# 2_waffling60-MXHS-ANSI_matrix.net
KiCad netlist of a schematic drawn in Altium Designer
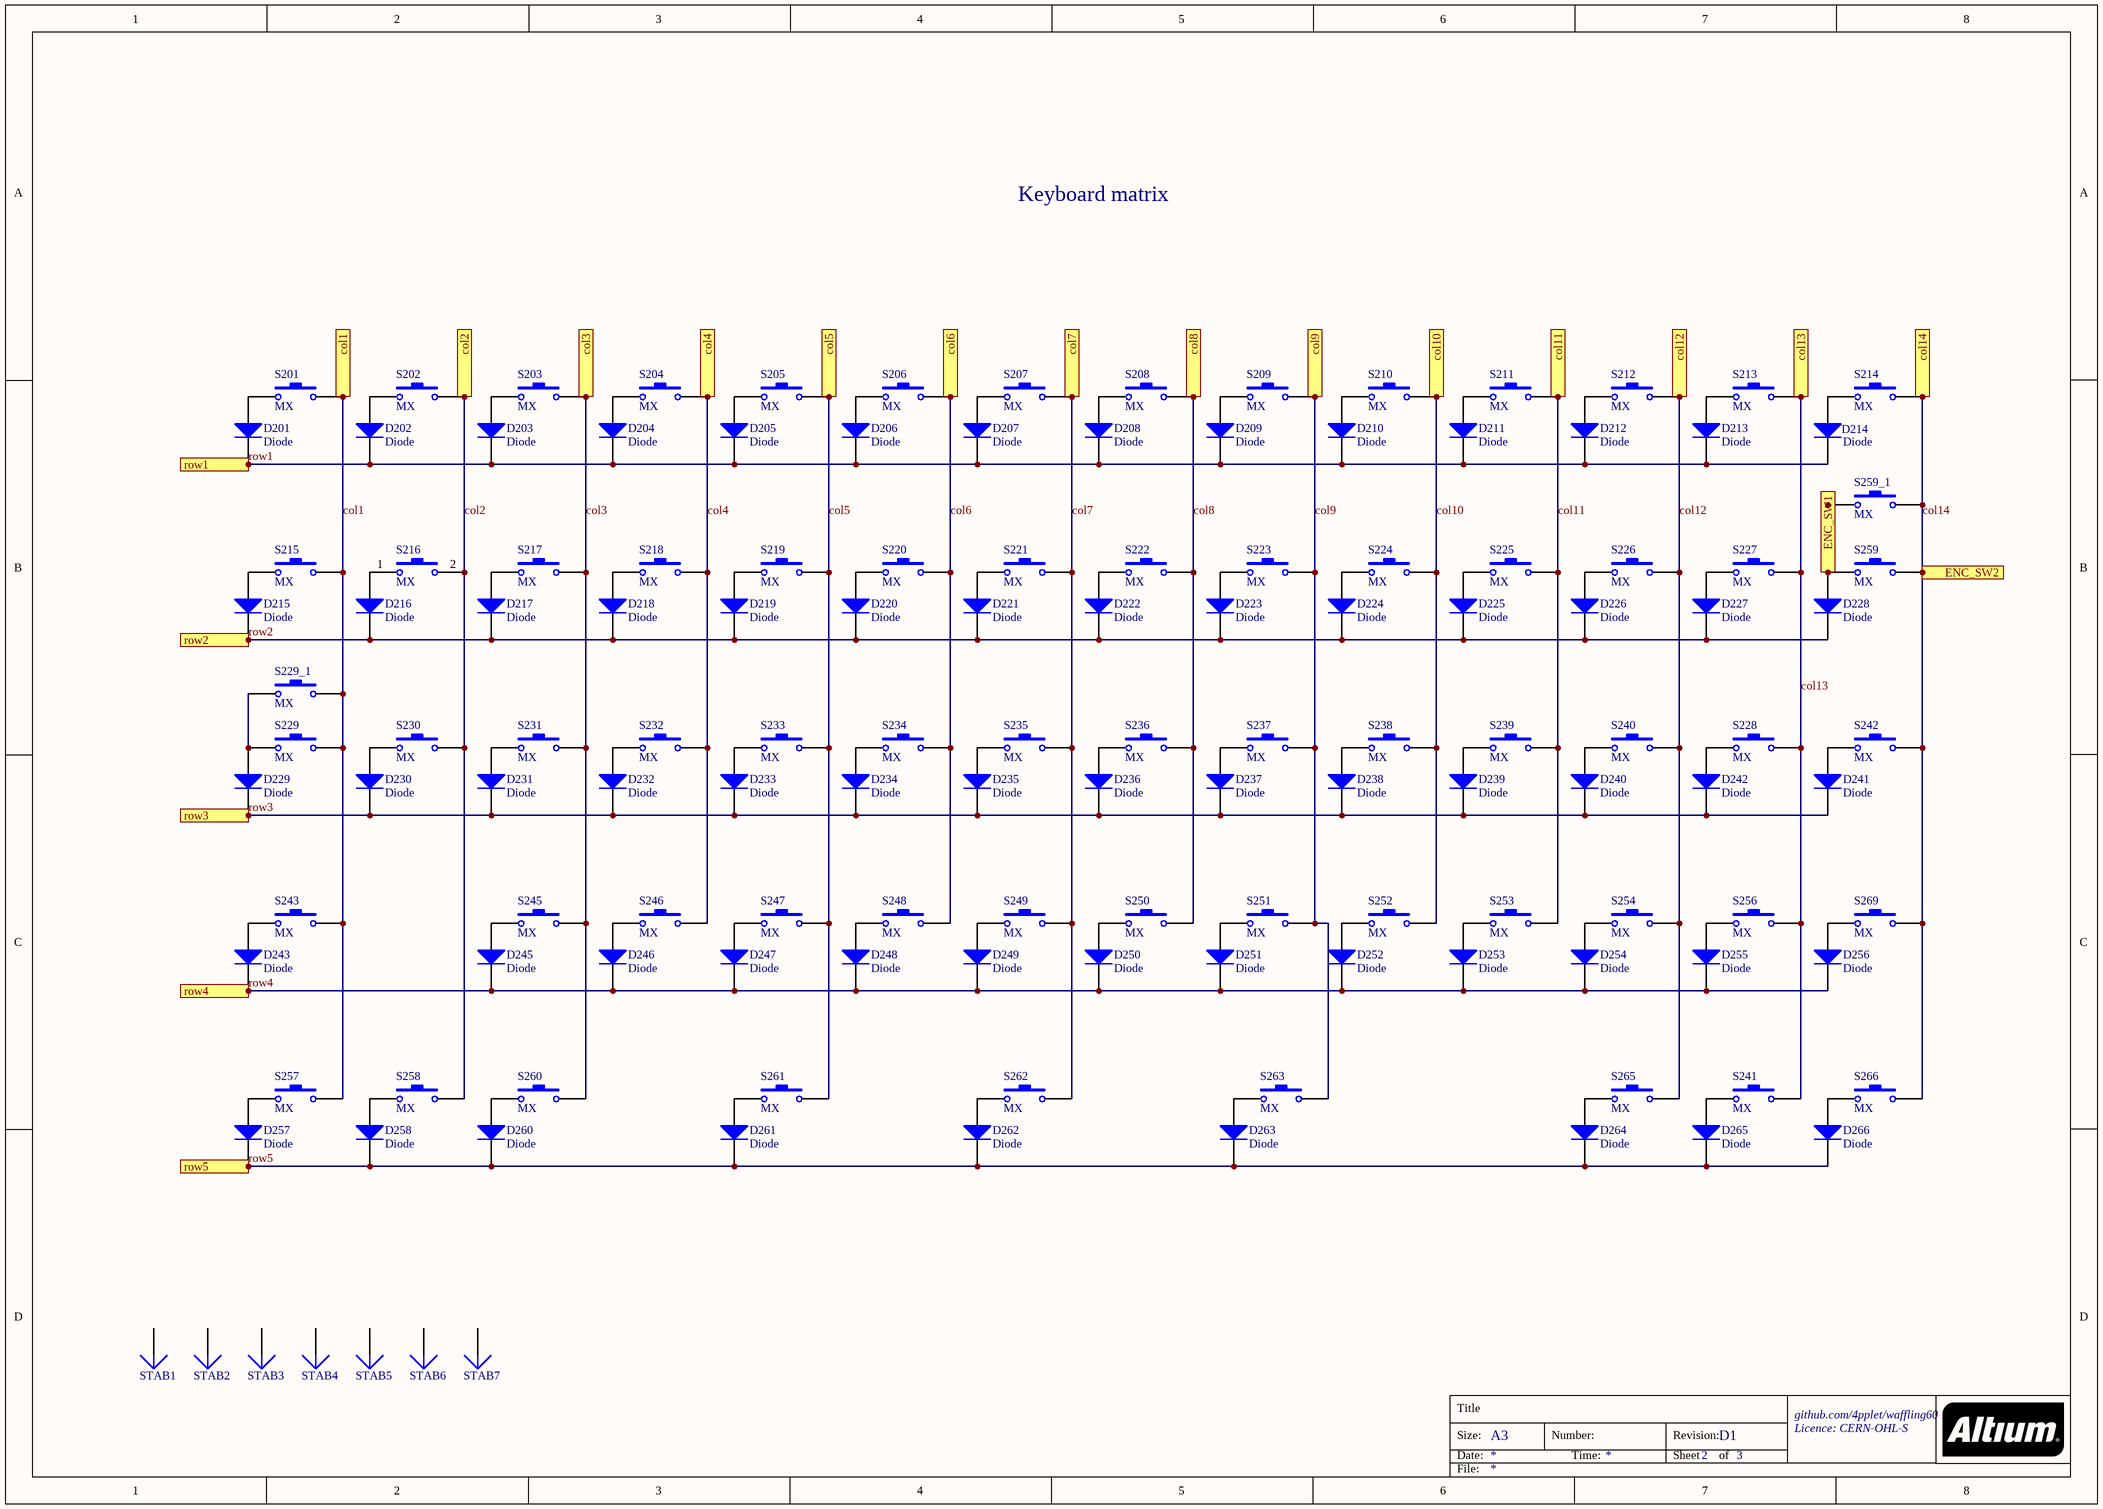
[diagram p0: 2_waffling60-MXHS-ANSI_matrix.SchDoc]

(export (version "E")
  (design (tool "Eeschema 10.0.6"))
  (components
    (comp (ref "D201")
      (value "Diode")
      (footprint "SOD-123")
      (description "Default Diode")
      (fields (field (name "LCSC PART #") "C81598") (field (name "MRF.PART") "1N4148W"))
      (libsource (lib "Miscellaneous Devices") (part "Diode"))
    )
    (comp (ref "D202")
      (value "Diode")
      (footprint "SOD-123")
      (description "Default Diode")
      (fields (field (name "LCSC PART #") "C81598") (field (name "MRF.PART") "1N4148W"))
      (libsource (lib "Miscellaneous Devices") (part "Diode"))
    )
    (comp (ref "D203")
      (value "Diode")
      (footprint "SOD-123")
      (description "Default Diode")
      (fields (field (name "LCSC PART #") "C81598") (field (name "MRF.PART") "1N4148W"))
      (libsource (lib "Miscellaneous Devices") (part "Diode"))
    )
    (comp (ref "D204")
      (value "Diode")
      (footprint "SOD-123")
      (description "Default Diode")
      (fields (field (name "LCSC PART #") "C81598") (field (name "MRF.PART") "1N4148W"))
      (libsource (lib "Miscellaneous Devices") (part "Diode"))
    )
    (comp (ref "D205")
      (value "Diode")
      (footprint "SOD-123")
      (description "Default Diode")
      (fields (field (name "LCSC PART #") "C81598") (field (name "MRF.PART") "1N4148W"))
      (libsource (lib "Miscellaneous Devices") (part "Diode"))
    )
    (comp (ref "D206")
      (value "Diode")
      (footprint "SOD-123")
      (description "Default Diode")
      (fields (field (name "LCSC PART #") "C81598") (field (name "MRF.PART") "1N4148W"))
      (libsource (lib "Miscellaneous Devices") (part "Diode"))
    )
    (comp (ref "D207")
      (value "Diode")
      (footprint "SOD-123")
      (description "Default Diode")
      (fields (field (name "LCSC PART #") "C81598") (field (name "MRF.PART") "1N4148W"))
      (libsource (lib "Miscellaneous Devices") (part "Diode"))
    )
    (comp (ref "D208")
      (value "Diode")
      (footprint "SOD-123")
      (description "Default Diode")
      (fields (field (name "LCSC PART #") "C81598") (field (name "MRF.PART") "1N4148W"))
      (libsource (lib "Miscellaneous Devices") (part "Diode"))
    )
    (comp (ref "D209")
      (value "Diode")
      (footprint "SOD-123")
      (description "Default Diode")
      (fields (field (name "LCSC PART #") "C81598") (field (name "MRF.PART") "1N4148W"))
      (libsource (lib "Miscellaneous Devices") (part "Diode"))
    )
    (comp (ref "D210")
      (value "Diode")
      (footprint "SOD-123")
      (description "Default Diode")
      (fields (field (name "LCSC PART #") "C81598") (field (name "MRF.PART") "1N4148W"))
      (libsource (lib "Miscellaneous Devices") (part "Diode"))
    )
    (comp (ref "D211")
      (value "Diode")
      (footprint "SOD-123")
      (description "Default Diode")
      (fields (field (name "LCSC PART #") "C81598") (field (name "MRF.PART") "1N4148W"))
      (libsource (lib "Miscellaneous Devices") (part "Diode"))
    )
    (comp (ref "D212")
      (value "Diode")
      (footprint "SOD-123")
      (description "Default Diode")
      (fields (field (name "LCSC PART #") "C81598") (field (name "MRF.PART") "1N4148W"))
      (libsource (lib "Miscellaneous Devices") (part "Diode"))
    )
    (comp (ref "D213")
      (value "Diode")
      (footprint "SOD-123")
      (description "Default Diode")
      (fields (field (name "LCSC PART #") "C81598") (field (name "MRF.PART") "1N4148W"))
      (libsource (lib "Miscellaneous Devices") (part "Diode"))
    )
    (comp (ref "D214")
      (value "Diode")
      (footprint "SOD-123")
      (description "Default Diode")
      (fields (field (name "LCSC PART #") "C81598") (field (name "MRF.PART") "1N4148W"))
      (libsource (lib "Miscellaneous Devices") (part "Diode"))
    )
    (comp (ref "D215")
      (value "Diode")
      (footprint "SOD-123")
      (description "Default Diode")
      (fields (field (name "LCSC PART #") "C81598") (field (name "MRF.PART") "1N4148W"))
      (libsource (lib "Miscellaneous Devices") (part "Diode"))
    )
    (comp (ref "D216")
      (value "Diode")
      (footprint "SOD-123")
      (description "Default Diode")
      (fields (field (name "LCSC PART #") "C81598") (field (name "MRF.PART") "1N4148W"))
      (libsource (lib "Miscellaneous Devices") (part "Diode"))
    )
    (comp (ref "D217")
      (value "Diode")
      (footprint "SOD-123")
      (description "Default Diode")
      (fields (field (name "LCSC PART #") "C81598") (field (name "MRF.PART") "1N4148W"))
      (libsource (lib "Miscellaneous Devices") (part "Diode"))
    )
    (comp (ref "D218")
      (value "Diode")
      (footprint "SOD-123")
      (description "Default Diode")
      (fields (field (name "LCSC PART #") "C81598") (field (name "MRF.PART") "1N4148W"))
      (libsource (lib "Miscellaneous Devices") (part "Diode"))
    )
    (comp (ref "D219")
      (value "Diode")
      (footprint "SOD-123")
      (description "Default Diode")
      (fields (field (name "LCSC PART #") "C81598") (field (name "MRF.PART") "1N4148W"))
      (libsource (lib "Miscellaneous Devices") (part "Diode"))
    )
    (comp (ref "D220")
      (value "Diode")
      (footprint "SOD-123")
      (description "Default Diode")
      (fields (field (name "LCSC PART #") "C81598") (field (name "MRF.PART") "1N4148W"))
      (libsource (lib "Miscellaneous Devices") (part "Diode"))
    )
    (comp (ref "D221")
      (value "Diode")
      (footprint "SOD-123")
      (description "Default Diode")
      (fields (field (name "LCSC PART #") "C81598") (field (name "MRF.PART") "1N4148W"))
      (libsource (lib "Miscellaneous Devices") (part "Diode"))
    )
    (comp (ref "D222")
      (value "Diode")
      (footprint "SOD-123")
      (description "Default Diode")
      (fields (field (name "LCSC PART #") "C81598") (field (name "MRF.PART") "1N4148W"))
      (libsource (lib "Miscellaneous Devices") (part "Diode"))
    )
    (comp (ref "D223")
      (value "Diode")
      (footprint "SOD-123")
      (description "Default Diode")
      (fields (field (name "LCSC PART #") "C81598") (field (name "MRF.PART") "1N4148W"))
      (libsource (lib "Miscellaneous Devices") (part "Diode"))
    )
    (comp (ref "D224")
      (value "Diode")
      (footprint "SOD-123")
      (description "Default Diode")
      (fields (field (name "LCSC PART #") "C81598") (field (name "MRF.PART") "1N4148W"))
      (libsource (lib "Miscellaneous Devices") (part "Diode"))
    )
    (comp (ref "D225")
      (value "Diode")
      (footprint "SOD-123")
      (description "Default Diode")
      (fields (field (name "LCSC PART #") "C81598") (field (name "MRF.PART") "1N4148W"))
      (libsource (lib "Miscellaneous Devices") (part "Diode"))
    )
    (comp (ref "D226")
      (value "Diode")
      (footprint "SOD-123")
      (description "Default Diode")
      (fields (field (name "LCSC PART #") "C81598") (field (name "MRF.PART") "1N4148W"))
      (libsource (lib "Miscellaneous Devices") (part "Diode"))
    )
    (comp (ref "D227")
      (value "Diode")
      (footprint "SOD-123")
      (description "Default Diode")
      (fields (field (name "LCSC PART #") "C81598") (field (name "MRF.PART") "1N4148W"))
      (libsource (lib "Miscellaneous Devices") (part "Diode"))
    )
    (comp (ref "D228")
      (value "Diode")
      (footprint "SOD-123")
      (description "Default Diode")
      (fields (field (name "LCSC PART #") "C81598") (field (name "MRF.PART") "1N4148W"))
      (libsource (lib "Miscellaneous Devices") (part "Diode"))
    )
    (comp (ref "D229")
      (value "Diode")
      (footprint "SOD-123")
      (description "Default Diode")
      (fields (field (name "LCSC PART #") "C81598") (field (name "MRF.PART") "1N4148W"))
      (libsource (lib "Miscellaneous Devices") (part "Diode"))
    )
    (comp (ref "D230")
      (value "Diode")
      (footprint "SOD-123")
      (description "Default Diode")
      (fields (field (name "LCSC PART #") "C81598") (field (name "MRF.PART") "1N4148W"))
      (libsource (lib "Miscellaneous Devices") (part "Diode"))
    )
    (comp (ref "D231")
      (value "Diode")
      (footprint "SOD-123")
      (description "Default Diode")
      (fields (field (name "LCSC PART #") "C81598") (field (name "MRF.PART") "1N4148W"))
      (libsource (lib "Miscellaneous Devices") (part "Diode"))
    )
    (comp (ref "D232")
      (value "Diode")
      (footprint "SOD-123")
      (description "Default Diode")
      (fields (field (name "LCSC PART #") "C81598") (field (name "MRF.PART") "1N4148W"))
      (libsource (lib "Miscellaneous Devices") (part "Diode"))
    )
    (comp (ref "D233")
      (value "Diode")
      (footprint "SOD-123")
      (description "Default Diode")
      (fields (field (name "LCSC PART #") "C81598") (field (name "MRF.PART") "1N4148W"))
      (libsource (lib "Miscellaneous Devices") (part "Diode"))
    )
    (comp (ref "D234")
      (value "Diode")
      (footprint "SOD-123")
      (description "Default Diode")
      (fields (field (name "LCSC PART #") "C81598") (field (name "MRF.PART") "1N4148W"))
      (libsource (lib "Miscellaneous Devices") (part "Diode"))
    )
    (comp (ref "D235")
      (value "Diode")
      (footprint "SOD-123")
      (description "Default Diode")
      (fields (field (name "LCSC PART #") "C81598") (field (name "MRF.PART") "1N4148W"))
      (libsource (lib "Miscellaneous Devices") (part "Diode"))
    )
    (comp (ref "D236")
      (value "Diode")
      (footprint "SOD-123")
      (description "Default Diode")
      (fields (field (name "LCSC PART #") "C81598") (field (name "MRF.PART") "1N4148W"))
      (libsource (lib "Miscellaneous Devices") (part "Diode"))
    )
    (comp (ref "D237")
      (value "Diode")
      (footprint "SOD-123")
      (description "Default Diode")
      (fields (field (name "LCSC PART #") "C81598") (field (name "MRF.PART") "1N4148W"))
      (libsource (lib "Miscellaneous Devices") (part "Diode"))
    )
    (comp (ref "D238")
      (value "Diode")
      (footprint "SOD-123")
      (description "Default Diode")
      (fields (field (name "LCSC PART #") "C81598") (field (name "MRF.PART") "1N4148W"))
      (libsource (lib "Miscellaneous Devices") (part "Diode"))
    )
    (comp (ref "D239")
      (value "Diode")
      (footprint "SOD-123")
      (description "Default Diode")
      (fields (field (name "LCSC PART #") "C81598") (field (name "MRF.PART") "1N4148W"))
      (libsource (lib "Miscellaneous Devices") (part "Diode"))
    )
    (comp (ref "D240")
      (value "Diode")
      (footprint "SOD-123")
      (description "Default Diode")
      (fields (field (name "LCSC PART #") "C81598") (field (name "MRF.PART") "1N4148W"))
      (libsource (lib "Miscellaneous Devices") (part "Diode"))
    )
    (comp (ref "D241")
      (value "Diode")
      (footprint "SOD-123")
      (description "Default Diode")
      (fields (field (name "LCSC PART #") "C81598") (field (name "MRF.PART") "1N4148W"))
      (libsource (lib "Miscellaneous Devices") (part "Diode"))
    )
    (comp (ref "D242")
      (value "Diode")
      (footprint "SOD-123")
      (description "Default Diode")
      (fields (field (name "LCSC PART #") "C81598") (field (name "MRF.PART") "1N4148W"))
      (libsource (lib "Miscellaneous Devices") (part "Diode"))
    )
    (comp (ref "D243")
      (value "Diode")
      (footprint "SOD-123")
      (description "Default Diode")
      (fields (field (name "LCSC PART #") "C81598") (field (name "MRF.PART") "1N4148W"))
      (libsource (lib "Miscellaneous Devices") (part "Diode"))
    )
    (comp (ref "D245")
      (value "Diode")
      (footprint "SOD-123")
      (description "Default Diode")
      (fields (field (name "LCSC PART #") "C81598") (field (name "MRF.PART") "1N4148W"))
      (libsource (lib "Miscellaneous Devices") (part "Diode"))
    )
    (comp (ref "D246")
      (value "Diode")
      (footprint "SOD-123")
      (description "Default Diode")
      (fields (field (name "LCSC PART #") "C81598") (field (name "MRF.PART") "1N4148W"))
      (libsource (lib "Miscellaneous Devices") (part "Diode"))
    )
    (comp (ref "D247")
      (value "Diode")
      (footprint "SOD-123")
      (description "Default Diode")
      (fields (field (name "LCSC PART #") "C81598") (field (name "MRF.PART") "1N4148W"))
      (libsource (lib "Miscellaneous Devices") (part "Diode"))
    )
    (comp (ref "D248")
      (value "Diode")
      (footprint "SOD-123")
      (description "Default Diode")
      (fields (field (name "LCSC PART #") "C81598") (field (name "MRF.PART") "1N4148W"))
      (libsource (lib "Miscellaneous Devices") (part "Diode"))
    )
    (comp (ref "D249")
      (value "Diode")
      (footprint "SOD-123")
      (description "Default Diode")
      (fields (field (name "LCSC PART #") "C81598") (field (name "MRF.PART") "1N4148W"))
      (libsource (lib "Miscellaneous Devices") (part "Diode"))
    )
    (comp (ref "D250")
      (value "Diode")
      (footprint "SOD-123")
      (description "Default Diode")
      (fields (field (name "LCSC PART #") "C81598") (field (name "MRF.PART") "1N4148W"))
      (libsource (lib "Miscellaneous Devices") (part "Diode"))
    )
    (comp (ref "D251")
      (value "Diode")
      (footprint "SOD-123")
      (description "Default Diode")
      (fields (field (name "LCSC PART #") "C81598") (field (name "MRF.PART") "1N4148W"))
      (libsource (lib "Miscellaneous Devices") (part "Diode"))
    )
    (comp (ref "D252")
      (value "Diode")
      (footprint "SOD-123")
      (description "Default Diode")
      (fields (field (name "LCSC PART #") "C81598") (field (name "MRF.PART") "1N4148W"))
      (libsource (lib "Miscellaneous Devices") (part "Diode"))
    )
    (comp (ref "D253")
      (value "Diode")
      (footprint "SOD-123")
      (description "Default Diode")
      (fields (field (name "LCSC PART #") "C81598") (field (name "MRF.PART") "1N4148W"))
      (libsource (lib "Miscellaneous Devices") (part "Diode"))
    )
    (comp (ref "D254")
      (value "Diode")
      (footprint "SOD-123")
      (description "Default Diode")
      (fields (field (name "LCSC PART #") "C81598") (field (name "MRF.PART") "1N4148W"))
      (libsource (lib "Miscellaneous Devices") (part "Diode"))
    )
    (comp (ref "D255")
      (value "Diode")
      (footprint "SOD-123")
      (description "Default Diode")
      (fields (field (name "LCSC PART #") "C81598") (field (name "MRF.PART") "1N4148W"))
      (libsource (lib "Miscellaneous Devices") (part "Diode"))
    )
    (comp (ref "D256")
      (value "Diode")
      (footprint "SOD-123")
      (description "Default Diode")
      (fields (field (name "LCSC PART #") "C81598") (field (name "MRF.PART") "1N4148W"))
      (libsource (lib "Miscellaneous Devices") (part "Diode"))
    )
    (comp (ref "D257")
      (value "Diode")
      (footprint "SOD-123")
      (description "Default Diode")
      (fields (field (name "LCSC PART #") "C81598") (field (name "MRF.PART") "1N4148W"))
      (libsource (lib "Miscellaneous Devices") (part "Diode"))
    )
    (comp (ref "D258")
      (value "Diode")
      (footprint "SOD-123")
      (description "Default Diode")
      (fields (field (name "LCSC PART #") "C81598") (field (name "MRF.PART") "1N4148W"))
      (libsource (lib "Miscellaneous Devices") (part "Diode"))
    )
    (comp (ref "D260")
      (value "Diode")
      (footprint "SOD-123")
      (description "Default Diode")
      (fields (field (name "LCSC PART #") "C81598") (field (name "MRF.PART") "1N4148W"))
      (libsource (lib "Miscellaneous Devices") (part "Diode"))
    )
    (comp (ref "D261")
      (value "Diode")
      (footprint "SOD-123")
      (description "Default Diode")
      (fields (field (name "LCSC PART #") "C81598") (field (name "MRF.PART") "1N4148W"))
      (libsource (lib "Miscellaneous Devices") (part "Diode"))
    )
    (comp (ref "D262")
      (value "Diode")
      (footprint "SOD-123")
      (description "Default Diode")
      (fields (field (name "LCSC PART #") "C81598") (field (name "MRF.PART") "1N4148W"))
      (libsource (lib "Miscellaneous Devices") (part "Diode"))
    )
    (comp (ref "D263")
      (value "Diode")
      (footprint "SOD-123")
      (description "Default Diode")
      (fields (field (name "LCSC PART #") "C81598") (field (name "MRF.PART") "1N4148W"))
      (libsource (lib "Miscellaneous Devices") (part "Diode"))
    )
    (comp (ref "D264")
      (value "Diode")
      (footprint "SOD-123")
      (description "Default Diode")
      (fields (field (name "LCSC PART #") "C81598") (field (name "MRF.PART") "1N4148W"))
      (libsource (lib "Miscellaneous Devices") (part "Diode"))
    )
    (comp (ref "D265")
      (value "Diode")
      (footprint "SOD-123")
      (description "Default Diode")
      (fields (field (name "LCSC PART #") "C81598") (field (name "MRF.PART") "1N4148W"))
      (libsource (lib "Miscellaneous Devices") (part "Diode"))
    )
    (comp (ref "D266")
      (value "Diode")
      (footprint "SOD-123")
      (description "Default Diode")
      (fields (field (name "LCSC PART #") "C81598") (field (name "MRF.PART") "1N4148W"))
      (libsource (lib "Miscellaneous Devices") (part "Diode"))
    )
    (comp (ref "S201")
      (value "MX")
      (footprint "MXHS-switch - 1U Top layer - AS2")
      (description "Switch")
      (fields (field (name "LCSC PART #") "C5156480") (field (name "MRF.PART") "CPG151101S11-16"))
      (libsource (lib "Miscellaneous Devices") (part "SW-PB"))
    )
    (comp (ref "S202")
      (value "MX")
      (footprint "MXHS-switch - 1U Top layer - switched pol AS2")
      (description "Switch")
      (fields (field (name "LCSC PART #") "C5156480") (field (name "MRF.PART") "CPG151101S11-16"))
      (libsource (lib "Miscellaneous Devices") (part "SW-PB"))
    )
    (comp (ref "S203")
      (value "MX")
      (footprint "MXHS-switch - 1U Top layer - AS2")
      (description "Switch")
      (fields (field (name "LCSC PART #") "C5156480") (field (name "MRF.PART") "CPG151101S11-16"))
      (libsource (lib "Miscellaneous Devices") (part "SW-PB"))
    )
    (comp (ref "S204")
      (value "MX")
      (footprint "MXHS-switch - 1U Top layer - switched pol AS2")
      (description "Switch")
      (fields (field (name "LCSC PART #") "C5156480") (field (name "MRF.PART") "CPG151101S11-16"))
      (libsource (lib "Miscellaneous Devices") (part "SW-PB"))
    )
    (comp (ref "S205")
      (value "MX")
      (footprint "MXHS-switch - 1U Top layer - AS2")
      (description "Switch")
      (fields (field (name "LCSC PART #") "C5156480") (field (name "MRF.PART") "CPG151101S11-16"))
      (libsource (lib "Miscellaneous Devices") (part "SW-PB"))
    )
    (comp (ref "S206")
      (value "MX")
      (footprint "MXHS-switch - 1U Top layer - AS2")
      (description "Switch")
      (fields (field (name "LCSC PART #") "C5156480") (field (name "MRF.PART") "CPG151101S11-16"))
      (libsource (lib "Miscellaneous Devices") (part "SW-PB"))
    )
    (comp (ref "S207")
      (value "MX")
      (footprint "MXHS-switch - 1U Top layer - AS2")
      (description "Switch")
      (fields (field (name "LCSC PART #") "C5156480") (field (name "MRF.PART") "CPG151101S11-16"))
      (libsource (lib "Miscellaneous Devices") (part "SW-PB"))
    )
    (comp (ref "S208")
      (value "MX")
      (footprint "MXHS-switch - 1U Top layer - AS2")
      (description "Switch")
      (fields (field (name "LCSC PART #") "C5156480") (field (name "MRF.PART") "CPG151101S11-16"))
      (libsource (lib "Miscellaneous Devices") (part "SW-PB"))
    )
    (comp (ref "S209")
      (value "MX")
      (footprint "MXHS-switch - 1U Top layer - AS2")
      (description "Switch")
      (fields (field (name "LCSC PART #") "C5156480") (field (name "MRF.PART") "CPG151101S11-16"))
      (libsource (lib "Miscellaneous Devices") (part "SW-PB"))
    )
    (comp (ref "S210")
      (value "MX")
      (footprint "MXHS-switch - 1U Top layer - AS2")
      (description "Switch")
      (fields (field (name "LCSC PART #") "C5156480") (field (name "MRF.PART") "CPG151101S11-16"))
      (libsource (lib "Miscellaneous Devices") (part "SW-PB"))
    )
    (comp (ref "S211")
      (value "MX")
      (footprint "MXHS-switch - 1U Top layer - switched pol AS2")
      (description "Switch")
      (fields (field (name "LCSC PART #") "C5156480") (field (name "MRF.PART") "CPG151101S11-16"))
      (libsource (lib "Miscellaneous Devices") (part "SW-PB"))
    )
    (comp (ref "S212")
      (value "MX")
      (footprint "MXHS-switch - 1U Top layer - AS2")
      (description "Switch")
      (fields (field (name "LCSC PART #") "C5156480") (field (name "MRF.PART") "CPG151101S11-16"))
      (libsource (lib "Miscellaneous Devices") (part "SW-PB"))
    )
    (comp (ref "S213")
      (value "MX")
      (footprint "MXHS-switch - 1U Top layer - AS2")
      (description "Switch")
      (fields (field (name "LCSC PART #") "C5156480") (field (name "MRF.PART") "CPG151101S11-16"))
      (libsource (lib "Miscellaneous Devices") (part "SW-PB"))
    )
    (comp (ref "S214")
      (value "MX")
      (footprint "MXHS-switch - 1U Top layer - AS2 - S2")
      (description "Switch")
      (fields (field (name "LCSC PART #") "C5156480") (field (name "MRF.PART") "CPG151101S11-16"))
      (libsource (lib "Miscellaneous Devices") (part "SW-PB"))
    )
    (comp (ref "S215")
      (value "MX")
      (footprint "MXHS-switch - 1U Top layer - AS2")
      (description "TAB")
      (fields (field (name "LCSC PART #") "C5156480") (field (name "MRF.PART") "CPG151101S11-16"))
      (libsource (lib "Miscellaneous Devices") (part "SW-PB"))
    )
    (comp (ref "S216")
      (value "MX")
      (footprint "MXHS-switch - 1U Top layer - switched pol AS2")
      (description "Switch")
      (fields (field (name "LCSC PART #") "C5156480") (field (name "MRF.PART") "CPG151101S11-16"))
      (libsource (lib "") (part "SW-PB_1"))
    )
    (comp (ref "S217")
      (value "MX")
      (footprint "MXHS-switch - 1U Top layer - AS2")
      (description "Switch")
      (fields (field (name "LCSC PART #") "C5156480") (field (name "MRF.PART") "CPG151101S11-16"))
      (libsource (lib "Miscellaneous Devices") (part "SW-PB"))
    )
    (comp (ref "S218")
      (value "MX")
      (footprint "MXHS-switch - 1U Top layer - AS2")
      (description "Switch")
      (fields (field (name "LCSC PART #") "C5156480") (field (name "MRF.PART") "CPG151101S11-16"))
      (libsource (lib "Miscellaneous Devices") (part "SW-PB"))
    )
    (comp (ref "S219")
      (value "MX")
      (footprint "MXHS-switch - 1U Top layer - AS2")
      (description "Switch")
      (fields (field (name "LCSC PART #") "C5156480") (field (name "MRF.PART") "CPG151101S11-16"))
      (libsource (lib "Miscellaneous Devices") (part "SW-PB"))
    )
    (comp (ref "S220")
      (value "MX")
      (footprint "MXHS-switch - 1U Top layer - switched pol AS2")
      (description "Switch")
      (fields (field (name "LCSC PART #") "C5156480") (field (name "MRF.PART") "CPG151101S11-16"))
      (libsource (lib "Miscellaneous Devices") (part "SW-PB"))
    )
    (comp (ref "S221")
      (value "MX")
      (footprint "MXHS-switch - 1U Top layer - AS2")
      (description "Switch")
      (fields (field (name "LCSC PART #") "C5156480") (field (name "MRF.PART") "CPG151101S11-16"))
      (libsource (lib "Miscellaneous Devices") (part "SW-PB"))
    )
    (comp (ref "S222")
      (value "MX")
      (footprint "MXHS-switch - 1U Top layer - switched pol AS2")
      (description "Switch")
      (fields (field (name "LCSC PART #") "C5156480") (field (name "MRF.PART") "CPG151101S11-16"))
      (libsource (lib "Miscellaneous Devices") (part "SW-PB"))
    )
    (comp (ref "S223")
      (value "MX")
      (footprint "MXHS-switch - 1U Top layer - AS2")
      (description "Switch")
      (fields (field (name "LCSC PART #") "C5156480") (field (name "MRF.PART") "CPG151101S11-16"))
      (libsource (lib "Miscellaneous Devices") (part "SW-PB"))
    )
    (comp (ref "S224")
      (value "MX")
      (footprint "MXHS-switch - 1U Top layer - AS2")
      (description "Switch")
      (fields (field (name "LCSC PART #") "C5156480") (field (name "MRF.PART") "CPG151101S11-16"))
      (libsource (lib "Miscellaneous Devices") (part "SW-PB"))
    )
    (comp (ref "S225")
      (value "MX")
      (footprint "MXHS-switch - 1U Top layer - AS2")
      (description "Switch")
      (fields (field (name "LCSC PART #") "C5156480") (field (name "MRF.PART") "CPG151101S11-16"))
      (libsource (lib "Miscellaneous Devices") (part "SW-PB"))
    )
    (comp (ref "S226")
      (value "MX")
      (footprint "MXHS-switch - 1U Top layer - AS2")
      (description "Switch")
      (fields (field (name "LCSC PART #") "C5156480") (field (name "MRF.PART") "CPG151101S11-16"))
      (libsource (lib "Miscellaneous Devices") (part "SW-PB"))
    )
    (comp (ref "S227")
      (value "MX")
      (footprint "MXHS-switch - 1U Top layer - switched pol AS2")
      (description "Switch")
      (fields (field (name "LCSC PART #") "C5156480") (field (name "MRF.PART") "CPG151101S11-16"))
      (libsource (lib "Miscellaneous Devices") (part "SW-PB"))
    )
    (comp (ref "S228")
      (value "MX")
      (footprint "MXHS-switch - 1U Top layer - AS2 - S2")
      (description "Switch")
      (fields (field (name "LCSC PART #") "C5156480") (field (name "MRF.PART") "CPG151101S11-16"))
      (libsource (lib "Miscellaneous Devices") (part "SW-PB"))
    )
    (comp (ref "S229")
      (value "MX")
      (footprint "MXHS-switch - 1U Top layer - AS2")
      (description "Switch")
      (fields (field (name "LCSC PART #") "C5156480") (field (name "MRF.PART") "CPG151101S11-16"))
      (libsource (lib "Miscellaneous Devices") (part "SW-PB"))
    )
    (comp (ref "S229_1")
      (value "MX")
      (footprint "MXHS-switch - 1U Top layer - AS2")
      (description "Switch")
      (fields (field (name "LCSC PART #") "C5156480") (field (name "MRF.PART") "CPG151101S11-16"))
      (libsource (lib "Miscellaneous Devices") (part "SW-PB"))
    )
    (comp (ref "S230")
      (value "MX")
      (footprint "MXHS-switch - 1U Top layer - switched pol AS2")
      (description "Switch")
      (fields (field (name "LCSC PART #") "C5156480") (field (name "MRF.PART") "CPG151101S11-16"))
      (libsource (lib "Miscellaneous Devices") (part "SW-PB"))
    )
    (comp (ref "S231")
      (value "MX")
      (footprint "MXHS-switch - 1U Top layer - AS2")
      (description "Switch")
      (fields (field (name "LCSC PART #") "C5156480") (field (name "MRF.PART") "CPG151101S11-16"))
      (libsource (lib "Miscellaneous Devices") (part "SW-PB"))
    )
    (comp (ref "S232")
      (value "MX")
      (footprint "MXHS-switch - 1U Top layer - AS2")
      (description "Switch")
      (fields (field (name "LCSC PART #") "C5156480") (field (name "MRF.PART") "CPG151101S11-16"))
      (libsource (lib "Miscellaneous Devices") (part "SW-PB"))
    )
    (comp (ref "S233")
      (value "MX")
      (footprint "MXHS-switch - 1U Top layer - AS2")
      (description "Switch")
      (fields (field (name "LCSC PART #") "C5156480") (field (name "MRF.PART") "CPG151101S11-16"))
      (libsource (lib "Miscellaneous Devices") (part "SW-PB"))
    )
    (comp (ref "S234")
      (value "MX")
      (footprint "MXHS-switch - 1U Top layer - switched pol AS2")
      (description "Switch")
      (fields (field (name "LCSC PART #") "C5156480") (field (name "MRF.PART") "CPG151101S11-16"))
      (libsource (lib "Miscellaneous Devices") (part "SW-PB"))
    )
    (comp (ref "S235")
      (value "MX")
      (footprint "MXHS-switch - 1U Top layer - AS2 - S2")
      (description "Switch")
      (fields (field (name "LCSC PART #") "C5156480") (field (name "MRF.PART") "CPG151101S11-16"))
      (libsource (lib "Miscellaneous Devices") (part "SW-PB"))
    )
    (comp (ref "S236")
      (value "MX")
      (footprint "MXHS-switch - 1U Top layer - AS2")
      (description "Switch")
      (fields (field (name "LCSC PART #") "C5156480") (field (name "MRF.PART") "CPG151101S11-16"))
      (libsource (lib "Miscellaneous Devices") (part "SW-PB"))
    )
    (comp (ref "S237")
      (value "MX")
      (footprint "MXHS-switch - 1U Top layer - AS2")
      (description "Switch")
      (fields (field (name "LCSC PART #") "C5156480") (field (name "MRF.PART") "CPG151101S11-16"))
      (libsource (lib "Miscellaneous Devices") (part "SW-PB"))
    )
    (comp (ref "S238")
      (value "MX")
      (footprint "MXHS-switch - 1U Top layer - AS2")
      (description "Switch")
      (fields (field (name "LCSC PART #") "C5156480") (field (name "MRF.PART") "CPG151101S11-16"))
      (libsource (lib "Miscellaneous Devices") (part "SW-PB"))
    )
    (comp (ref "S239")
      (value "MX")
      (footprint "MXHS-switch - 1U Top layer - AS2")
      (description "Switch")
      (fields (field (name "LCSC PART #") "C5156480") (field (name "MRF.PART") "CPG151101S11-16"))
      (libsource (lib "Miscellaneous Devices") (part "SW-PB"))
    )
    (comp (ref "S240")
      (value "MX")
      (footprint "MXHS-switch - 1U Top layer - AS2")
      (description "Switch")
      (fields (field (name "LCSC PART #") "C5156480") (field (name "MRF.PART") "CPG151101S11-16"))
      (libsource (lib "Miscellaneous Devices") (part "SW-PB"))
    )
    (comp (ref "S241")
      (value "MX")
      (footprint "MXHS-switch - 1U Top layer - AS2")
      (description "Switch")
      (fields (field (name "LCSC PART #") "C5156480") (field (name "MRF.PART") "CPG151101S11-16"))
      (libsource (lib "Miscellaneous Devices") (part "SW-PB"))
    )
    (comp (ref "S242")
      (value "MX")
      (footprint "MXHS-switch - 1U Top layer - AS2 - S2")
      (description "Switch")
      (fields (field (name "LCSC PART #") "C5156480") (field (name "MRF.PART") "CPG151101S11-16"))
      (libsource (lib "Miscellaneous Devices") (part "SW-PB"))
    )
    (comp (ref "S243")
      (value "MX")
      (footprint "MXHS-switch - 1U Top layer - AS2")
      (description "Switch")
      (fields (field (name "LCSC PART #") "C5156480") (field (name "MRF.PART") "CPG151101S11-16"))
      (libsource (lib "Miscellaneous Devices") (part "SW-PB"))
    )
    (comp (ref "S245")
      (value "MX")
      (footprint "MXHS-switch - 1U Top layer - AS2")
      (description "Switch")
      (fields (field (name "LCSC PART #") "C5156480") (field (name "MRF.PART") "CPG151101S11-16"))
      (libsource (lib "Miscellaneous Devices") (part "SW-PB"))
    )
    (comp (ref "S246")
      (value "MX")
      (footprint "MXHS-switch - 1U Top layer - AS2")
      (description "Switch")
      (fields (field (name "LCSC PART #") "C5156480") (field (name "MRF.PART") "CPG151101S11-16"))
      (libsource (lib "Miscellaneous Devices") (part "SW-PB"))
    )
    (comp (ref "S247")
      (value "MX")
      (footprint "MXHS-switch - 1U Top layer - AS2")
      (description "Switch")
      (fields (field (name "LCSC PART #") "C5156480") (field (name "MRF.PART") "CPG151101S11-16"))
      (libsource (lib "Miscellaneous Devices") (part "SW-PB"))
    )
    (comp (ref "S248")
      (value "MX")
      (footprint "MXHS-switch - 1U Top layer - AS2")
      (description "Switch")
      (fields (field (name "LCSC PART #") "C5156480") (field (name "MRF.PART") "CPG151101S11-16"))
      (libsource (lib "Miscellaneous Devices") (part "SW-PB"))
    )
    (comp (ref "S249")
      (value "MX")
      (footprint "MXHS-switch - 1U Top layer - AS2")
      (description "Switch")
      (fields (field (name "LCSC PART #") "C5156480") (field (name "MRF.PART") "CPG151101S11-16"))
      (libsource (lib "Miscellaneous Devices") (part "SW-PB"))
    )
    (comp (ref "S250")
      (value "MX")
      (footprint "MXHS-switch - 1U Top layer - AS2")
      (description "Switch")
      (fields (field (name "LCSC PART #") "C5156480") (field (name "MRF.PART") "CPG151101S11-16"))
      (libsource (lib "Miscellaneous Devices") (part "SW-PB"))
    )
    (comp (ref "S251")
      (value "MX")
      (footprint "MXHS-switch - 1U Top layer - AS2")
      (description "Switch")
      (fields (field (name "LCSC PART #") "C5156480") (field (name "MRF.PART") "CPG151101S11-16"))
      (libsource (lib "Miscellaneous Devices") (part "SW-PB"))
    )
    (comp (ref "S252")
      (value "MX")
      (footprint "MXHS-switch - 1U Top layer - AS2")
      (description "Switch")
      (fields (field (name "LCSC PART #") "C5156480") (field (name "MRF.PART") "CPG151101S11-16"))
      (libsource (lib "Miscellaneous Devices") (part "SW-PB"))
    )
    (comp (ref "S253")
      (value "MX")
      (footprint "MXHS-switch - 1U Top layer - AS2")
      (description "Switch")
      (fields (field (name "LCSC PART #") "C5156480") (field (name "MRF.PART") "CPG151101S11-16"))
      (libsource (lib "Miscellaneous Devices") (part "SW-PB"))
    )
    (comp (ref "S254")
      (value "MX")
      (footprint "MXHS-switch - 1U Top layer - AS2")
      (description "Switch")
      (fields (field (name "LCSC PART #") "C5156480") (field (name "MRF.PART") "CPG151101S11-16"))
      (libsource (lib "Miscellaneous Devices") (part "SW-PB"))
    )
    (comp (ref "S256")
      (value "MX")
      (footprint "MXHS-switch - 1U Top layer - AS2")
      (description "Switch")
      (fields (field (name "LCSC PART #") "C5156480") (field (name "MRF.PART") "CPG151101S11-16"))
      (libsource (lib "Miscellaneous Devices") (part "SW-PB"))
    )
    (comp (ref "S257")
      (value "MX")
      (footprint "MXHS-switch - 1U Top layer - switched pol AS2")
      (description "Switch")
      (fields (field (name "LCSC PART #") "C5156480") (field (name "MRF.PART") "CPG151101S11-16"))
      (libsource (lib "Miscellaneous Devices") (part "SW-PB"))
    )
    (comp (ref "S258")
      (value "MX")
      (footprint "MXHS-switch - 1U Top layer - AS2")
      (description "Switch")
      (fields (field (name "LCSC PART #") "C5156480") (field (name "MRF.PART") "CPG151101S11-16"))
      (libsource (lib "Miscellaneous Devices") (part "SW-PB"))
    )
    (comp (ref "S259")
      (value "MX")
      (footprint "MXHS-switch - 1U Top layer - AS2 - S2")
      (description "Switch")
      (fields (field (name "LCSC PART #") "C5156480") (field (name "MRF.PART") "CPG151101S11-16"))
      (libsource (lib "Miscellaneous Devices") (part "SW-PB"))
    )
    (comp (ref "S259_1")
      (value "MX")
      (footprint "MXHS-switch - 1U Top layer - AS2 - S1")
      (description "Switch")
      (fields (field (name "LCSC PART #") "C5156480") (field (name "MRF.PART") "CPG151101S11-16"))
      (libsource (lib "Miscellaneous Devices") (part "SW-PB"))
    )
    (comp (ref "S260")
      (value "MX")
      (footprint "MXHS-switch - 1U Top layer - AS2")
      (description "Switch")
      (fields (field (name "LCSC PART #") "C5156480") (field (name "MRF.PART") "CPG151101S11-16"))
      (libsource (lib "Miscellaneous Devices") (part "SW-PB"))
    )
    (comp (ref "S261")
      (value "MX")
      (footprint "MXHS-switch - 1U Top layer - switched pol AS2")
      (description "Switch")
      (fields (field (name "LCSC PART #") "C5156480") (field (name "MRF.PART") "CPG151101S11-16"))
      (libsource (lib "Miscellaneous Devices") (part "SW-PB"))
    )
    (comp (ref "S262")
      (value "MX")
      (footprint "MXHS-switch - 1U Top layer - switched pol AS2")
      (description "Switch")
      (fields (field (name "LCSC PART #") "C5156480") (field (name "MRF.PART") "CPG151101S11-16"))
      (libsource (lib "Miscellaneous Devices") (part "SW-PB"))
    )
    (comp (ref "S263")
      (value "MX")
      (footprint "MXHS-switch - 1U Top layer - switched pol AS2")
      (description "Switch")
      (fields (field (name "LCSC PART #") "C5156480") (field (name "MRF.PART") "CPG151101S11-16"))
      (libsource (lib "Miscellaneous Devices") (part "SW-PB"))
    )
    (comp (ref "S265")
      (value "MX")
      (footprint "MXHS-switch - 1U Top layer - switched pol AS2")
      (description "Switch")
      (fields (field (name "LCSC PART #") "C5156480") (field (name "MRF.PART") "CPG151101S11-16"))
      (libsource (lib "Miscellaneous Devices") (part "SW-PB"))
    )
    (comp (ref "S266")
      (value "MX")
      (footprint "MXHS-switch - 1U Top layer - switched pol AS2")
      (description "Switch")
      (fields (field (name "LCSC PART #") "C5156480") (field (name "MRF.PART") "CPG151101S11-16"))
      (libsource (lib "Miscellaneous Devices") (part "SW-PB"))
    )
    (comp (ref "S269")
      (value "MX")
      (footprint "MXHS-switch - 1U Top layer - AS2")
      (description "Switch")
      (fields (field (name "LCSC PART #") "C5156480") (field (name "MRF.PART") "CPG151101S11-16"))
      (libsource (lib "Miscellaneous Devices") (part "SW-PB"))
    )
    (comp (ref "STAB1")
      (value "Plug")
      (footprint "Stab 2u")
      (libsource (lib "Miscellaneous Connectors") (part "Plug"))
    )
    (comp (ref "STAB2")
      (value "Plug")
      (footprint "Stab 2u")
      (libsource (lib "Miscellaneous Connectors") (part "Plug"))
    )
    (comp (ref "STAB3")
      (value "Plug")
      (footprint "Stab 7U")
      (libsource (lib "Miscellaneous Connectors") (part "Plug"))
    )
    (comp (ref "STAB4")
      (value "Plug")
      (footprint "Stab 10U")
      (libsource (lib "Miscellaneous Connectors") (part "Plug"))
    )
    (comp (ref "STAB5")
      (value "Plug")
      (footprint "Stab 3u")
      (libsource (lib "Miscellaneous Connectors") (part "Plug"))
    )
    (comp (ref "STAB6")
      (value "Plug")
      (footprint "Stab 3u")
      (libsource (lib "Miscellaneous Connectors") (part "Plug"))
    )
    (comp (ref "STAB7")
      (value "Plug")
      (footprint "Stab 2u")
      (libsource (lib "Miscellaneous Connectors") (part "Plug"))
    )
  )
  (nets
    (net (code "1") (name "/ENC_SW1") (class "Default")
      (node (ref "D228") (pin "1") (pinfunction "A_1") (pintype "passive"))
      (node (ref "S259") (pin "2") (pinfunction "2_2") (pintype "passive"))
      (node (ref "S259_1") (pin "1") (pinfunction "1_1") (pintype "passive"))
    )
    (net (code "2") (name "/col1") (class "Default")
      (node (ref "S201") (pin "2") (pinfunction "2_2") (pintype "passive"))
      (node (ref "S215") (pin "2") (pinfunction "2_2") (pintype "passive"))
      (node (ref "S229") (pin "2") (pinfunction "2_2") (pintype "passive"))
      (node (ref "S229_1") (pin "1") (pinfunction "1_1") (pintype "passive"))
      (node (ref "S243") (pin "2") (pinfunction "2_2") (pintype "passive"))
      (node (ref "S257") (pin "1") (pinfunction "1_1") (pintype "passive"))
    )
    (net (code "3") (name "/col2") (class "Default")
      (node (ref "S202") (pin "2") (pinfunction "2_2") (pintype "passive"))
      (node (ref "S216") (pin "2") (pinfunction "2_2") (pintype "passive"))
      (node (ref "S230") (pin "2") (pinfunction "2_2") (pintype "passive"))
      (node (ref "S258") (pin "2") (pinfunction "2_2") (pintype "passive"))
    )
    (net (code "4") (name "/col3") (class "Default")
      (node (ref "S203") (pin "2") (pinfunction "2_2") (pintype "passive"))
      (node (ref "S217") (pin "2") (pinfunction "2_2") (pintype "passive"))
      (node (ref "S231") (pin "2") (pinfunction "2_2") (pintype "passive"))
      (node (ref "S245") (pin "2") (pinfunction "2_2") (pintype "passive"))
      (node (ref "S260") (pin "2") (pinfunction "2_2") (pintype "passive"))
    )
    (net (code "5") (name "/col4") (class "Default")
      (node (ref "S204") (pin "2") (pinfunction "2_2") (pintype "passive"))
      (node (ref "S218") (pin "2") (pinfunction "2_2") (pintype "passive"))
      (node (ref "S232") (pin "2") (pinfunction "2_2") (pintype "passive"))
      (node (ref "S246") (pin "2") (pinfunction "2_2") (pintype "passive"))
    )
    (net (code "6") (name "/col5") (class "Default")
      (node (ref "S205") (pin "2") (pinfunction "2_2") (pintype "passive"))
      (node (ref "S219") (pin "2") (pinfunction "2_2") (pintype "passive"))
      (node (ref "S233") (pin "2") (pinfunction "2_2") (pintype "passive"))
      (node (ref "S247") (pin "2") (pinfunction "2_2") (pintype "passive"))
      (node (ref "S261") (pin "2") (pinfunction "2_2") (pintype "passive"))
    )
    (net (code "7") (name "/col6") (class "Default")
      (node (ref "S206") (pin "2") (pinfunction "2_2") (pintype "passive"))
      (node (ref "S220") (pin "2") (pinfunction "2_2") (pintype "passive"))
      (node (ref "S234") (pin "2") (pinfunction "2_2") (pintype "passive"))
      (node (ref "S248") (pin "2") (pinfunction "2_2") (pintype "passive"))
    )
    (net (code "8") (name "/col7") (class "Default")
      (node (ref "S207") (pin "2") (pinfunction "2_2") (pintype "passive"))
      (node (ref "S221") (pin "2") (pinfunction "2_2") (pintype "passive"))
      (node (ref "S235") (pin "2") (pinfunction "2_2") (pintype "passive"))
      (node (ref "S249") (pin "2") (pinfunction "2_2") (pintype "passive"))
      (node (ref "S262") (pin "1") (pinfunction "1_1") (pintype "passive"))
    )
    (net (code "9") (name "/col8") (class "Default")
      (node (ref "S208") (pin "2") (pinfunction "2_2") (pintype "passive"))
      (node (ref "S222") (pin "2") (pinfunction "2_2") (pintype "passive"))
      (node (ref "S236") (pin "2") (pinfunction "2_2") (pintype "passive"))
      (node (ref "S250") (pin "2") (pinfunction "2_2") (pintype "passive"))
    )
    (net (code "10") (name "/col9") (class "Default")
      (node (ref "S209") (pin "2") (pinfunction "2_2") (pintype "passive"))
      (node (ref "S223") (pin "2") (pinfunction "2_2") (pintype "passive"))
      (node (ref "S237") (pin "2") (pinfunction "2_2") (pintype "passive"))
      (node (ref "S251") (pin "2") (pinfunction "2_2") (pintype "passive"))
      (node (ref "S263") (pin "2") (pinfunction "2_2") (pintype "passive"))
    )
    (net (code "11") (name "/col10") (class "Default")
      (node (ref "S210") (pin "2") (pinfunction "2_2") (pintype "passive"))
      (node (ref "S224") (pin "2") (pinfunction "2_2") (pintype "passive"))
      (node (ref "S238") (pin "2") (pinfunction "2_2") (pintype "passive"))
      (node (ref "S252") (pin "2") (pinfunction "2_2") (pintype "passive"))
    )
    (net (code "12") (name "/col11") (class "Default")
      (node (ref "S211") (pin "2") (pinfunction "2_2") (pintype "passive"))
      (node (ref "S225") (pin "2") (pinfunction "2_2") (pintype "passive"))
      (node (ref "S239") (pin "2") (pinfunction "2_2") (pintype "passive"))
      (node (ref "S253") (pin "2") (pinfunction "2_2") (pintype "passive"))
    )
    (net (code "13") (name "/col12") (class "Default")
      (node (ref "S212") (pin "2") (pinfunction "2_2") (pintype "passive"))
      (node (ref "S226") (pin "2") (pinfunction "2_2") (pintype "passive"))
      (node (ref "S240") (pin "2") (pinfunction "2_2") (pintype "passive"))
      (node (ref "S254") (pin "2") (pinfunction "2_2") (pintype "passive"))
      (node (ref "S265") (pin "2") (pinfunction "2_2") (pintype "passive"))
    )
    (net (code "14") (name "/col13") (class "Default")
      (node (ref "S213") (pin "2") (pinfunction "2_2") (pintype "passive"))
      (node (ref "S227") (pin "2") (pinfunction "2_2") (pintype "passive"))
      (node (ref "S228") (pin "2") (pinfunction "2_2") (pintype "passive"))
      (node (ref "S241") (pin "1") (pinfunction "1_1") (pintype "passive"))
      (node (ref "S256") (pin "2") (pinfunction "2_2") (pintype "passive"))
    )
    (net (code "15") (name "/col14") (class "Default")
      (node (ref "S214") (pin "1") (pinfunction "1_1") (pintype "passive"))
      (node (ref "S242") (pin "1") (pinfunction "1_1") (pintype "passive"))
      (node (ref "S259") (pin "1") (pinfunction "1_1") (pintype "passive"))
      (node (ref "S259_1") (pin "2") (pinfunction "2_2") (pintype "passive"))
      (node (ref "S266") (pin "2") (pinfunction "2_2") (pintype "passive"))
      (node (ref "S269") (pin "2") (pinfunction "2_2") (pintype "passive"))
    )
    (net (code "16") (name "/row1") (class "Default")
      (node (ref "D201") (pin "2") (pinfunction "K_2") (pintype "passive"))
      (node (ref "D202") (pin "2") (pinfunction "K_2") (pintype "passive"))
      (node (ref "D203") (pin "2") (pinfunction "K_2") (pintype "passive"))
      (node (ref "D204") (pin "2") (pinfunction "K_2") (pintype "passive"))
      (node (ref "D205") (pin "2") (pinfunction "K_2") (pintype "passive"))
      (node (ref "D206") (pin "2") (pinfunction "K_2") (pintype "passive"))
      (node (ref "D207") (pin "2") (pinfunction "K_2") (pintype "passive"))
      (node (ref "D208") (pin "2") (pinfunction "K_2") (pintype "passive"))
      (node (ref "D209") (pin "2") (pinfunction "K_2") (pintype "passive"))
      (node (ref "D210") (pin "2") (pinfunction "K_2") (pintype "passive"))
      (node (ref "D211") (pin "2") (pinfunction "K_2") (pintype "passive"))
      (node (ref "D212") (pin "2") (pinfunction "K_2") (pintype "passive"))
      (node (ref "D213") (pin "2") (pinfunction "K_2") (pintype "passive"))
      (node (ref "D214") (pin "2") (pinfunction "K_2") (pintype "passive"))
    )
    (net (code "17") (name "/row2") (class "Default")
      (node (ref "D215") (pin "2") (pinfunction "K_2") (pintype "passive"))
      (node (ref "D216") (pin "2") (pinfunction "K_2") (pintype "passive"))
      (node (ref "D217") (pin "2") (pinfunction "K_2") (pintype "passive"))
      (node (ref "D218") (pin "2") (pinfunction "K_2") (pintype "passive"))
      (node (ref "D219") (pin "2") (pinfunction "K_2") (pintype "passive"))
      (node (ref "D220") (pin "2") (pinfunction "K_2") (pintype "passive"))
      (node (ref "D221") (pin "2") (pinfunction "K_2") (pintype "passive"))
      (node (ref "D222") (pin "2") (pinfunction "K_2") (pintype "passive"))
      (node (ref "D223") (pin "2") (pinfunction "K_2") (pintype "passive"))
      (node (ref "D224") (pin "2") (pinfunction "K_2") (pintype "passive"))
      (node (ref "D225") (pin "2") (pinfunction "K_2") (pintype "passive"))
      (node (ref "D226") (pin "2") (pinfunction "K_2") (pintype "passive"))
      (node (ref "D227") (pin "2") (pinfunction "K_2") (pintype "passive"))
      (node (ref "D228") (pin "2") (pinfunction "K_2") (pintype "passive"))
    )
    (net (code "18") (name "/row3") (class "Default")
      (node (ref "D229") (pin "2") (pinfunction "K_2") (pintype "passive"))
      (node (ref "D230") (pin "2") (pinfunction "K_2") (pintype "passive"))
      (node (ref "D231") (pin "2") (pinfunction "K_2") (pintype "passive"))
      (node (ref "D232") (pin "2") (pinfunction "K_2") (pintype "passive"))
      (node (ref "D233") (pin "2") (pinfunction "K_2") (pintype "passive"))
      (node (ref "D234") (pin "2") (pinfunction "K_2") (pintype "passive"))
      (node (ref "D235") (pin "2") (pinfunction "K_2") (pintype "passive"))
      (node (ref "D236") (pin "2") (pinfunction "K_2") (pintype "passive"))
      (node (ref "D237") (pin "2") (pinfunction "K_2") (pintype "passive"))
      (node (ref "D238") (pin "2") (pinfunction "K_2") (pintype "passive"))
      (node (ref "D239") (pin "2") (pinfunction "K_2") (pintype "passive"))
      (node (ref "D240") (pin "2") (pinfunction "K_2") (pintype "passive"))
      (node (ref "D241") (pin "2") (pinfunction "K_2") (pintype "passive"))
      (node (ref "D242") (pin "2") (pinfunction "K_2") (pintype "passive"))
    )
    (net (code "19") (name "/row4") (class "Default")
      (node (ref "D243") (pin "2") (pinfunction "K_2") (pintype "passive"))
      (node (ref "D245") (pin "2") (pinfunction "K_2") (pintype "passive"))
      (node (ref "D246") (pin "2") (pinfunction "K_2") (pintype "passive"))
      (node (ref "D247") (pin "2") (pinfunction "K_2") (pintype "passive"))
      (node (ref "D248") (pin "2") (pinfunction "K_2") (pintype "passive"))
      (node (ref "D249") (pin "2") (pinfunction "K_2") (pintype "passive"))
      (node (ref "D250") (pin "2") (pinfunction "K_2") (pintype "passive"))
      (node (ref "D251") (pin "2") (pinfunction "K_2") (pintype "passive"))
      (node (ref "D252") (pin "2") (pinfunction "K_2") (pintype "passive"))
      (node (ref "D253") (pin "2") (pinfunction "K_2") (pintype "passive"))
      (node (ref "D254") (pin "2") (pinfunction "K_2") (pintype "passive"))
      (node (ref "D255") (pin "2") (pinfunction "K_2") (pintype "passive"))
      (node (ref "D256") (pin "2") (pinfunction "K_2") (pintype "passive"))
    )
    (net (code "20") (name "/row5") (class "Default")
      (node (ref "D257") (pin "2") (pinfunction "K_2") (pintype "passive"))
      (node (ref "D258") (pin "2") (pinfunction "K_2") (pintype "passive"))
      (node (ref "D260") (pin "2") (pinfunction "K_2") (pintype "passive"))
      (node (ref "D261") (pin "2") (pinfunction "K_2") (pintype "passive"))
      (node (ref "D262") (pin "2") (pinfunction "K_2") (pintype "passive"))
      (node (ref "D263") (pin "2") (pinfunction "K_2") (pintype "passive"))
      (node (ref "D264") (pin "2") (pinfunction "K_2") (pintype "passive"))
      (node (ref "D265") (pin "2") (pinfunction "K_2") (pintype "passive"))
      (node (ref "D266") (pin "2") (pinfunction "K_2") (pintype "passive"))
    )
    (net (code "21") (name "Net-(D201-A)") (class "Default")
      (node (ref "D201") (pin "1") (pinfunction "A_1") (pintype "passive"))
      (node (ref "S201") (pin "1") (pinfunction "1_1") (pintype "passive"))
    )
    (net (code "22") (name "Net-(D202-A)") (class "Default")
      (node (ref "D202") (pin "1") (pinfunction "A_1") (pintype "passive"))
      (node (ref "S202") (pin "1") (pinfunction "1_1") (pintype "passive"))
    )
    (net (code "23") (name "Net-(D203-A)") (class "Default")
      (node (ref "D203") (pin "1") (pinfunction "A_1") (pintype "passive"))
      (node (ref "S203") (pin "1") (pinfunction "1_1") (pintype "passive"))
    )
    (net (code "24") (name "Net-(D204-A)") (class "Default")
      (node (ref "D204") (pin "1") (pinfunction "A_1") (pintype "passive"))
      (node (ref "S204") (pin "1") (pinfunction "1_1") (pintype "passive"))
    )
    (net (code "25") (name "Net-(D205-A)") (class "Default")
      (node (ref "D205") (pin "1") (pinfunction "A_1") (pintype "passive"))
      (node (ref "S205") (pin "1") (pinfunction "1_1") (pintype "passive"))
    )
    (net (code "26") (name "Net-(D206-A)") (class "Default")
      (node (ref "D206") (pin "1") (pinfunction "A_1") (pintype "passive"))
      (node (ref "S206") (pin "1") (pinfunction "1_1") (pintype "passive"))
    )
    (net (code "27") (name "Net-(D207-A)") (class "Default")
      (node (ref "D207") (pin "1") (pinfunction "A_1") (pintype "passive"))
      (node (ref "S207") (pin "1") (pinfunction "1_1") (pintype "passive"))
    )
    (net (code "28") (name "Net-(D208-A)") (class "Default")
      (node (ref "D208") (pin "1") (pinfunction "A_1") (pintype "passive"))
      (node (ref "S208") (pin "1") (pinfunction "1_1") (pintype "passive"))
    )
    (net (code "29") (name "Net-(D209-A)") (class "Default")
      (node (ref "D209") (pin "1") (pinfunction "A_1") (pintype "passive"))
      (node (ref "S209") (pin "1") (pinfunction "1_1") (pintype "passive"))
    )
    (net (code "30") (name "Net-(D210-A)") (class "Default")
      (node (ref "D210") (pin "1") (pinfunction "A_1") (pintype "passive"))
      (node (ref "S210") (pin "1") (pinfunction "1_1") (pintype "passive"))
    )
    (net (code "31") (name "Net-(D211-A)") (class "Default")
      (node (ref "D211") (pin "1") (pinfunction "A_1") (pintype "passive"))
      (node (ref "S211") (pin "1") (pinfunction "1_1") (pintype "passive"))
    )
    (net (code "32") (name "Net-(D212-A)") (class "Default")
      (node (ref "D212") (pin "1") (pinfunction "A_1") (pintype "passive"))
      (node (ref "S212") (pin "1") (pinfunction "1_1") (pintype "passive"))
    )
    (net (code "33") (name "Net-(D213-A)") (class "Default")
      (node (ref "D213") (pin "1") (pinfunction "A_1") (pintype "passive"))
      (node (ref "S213") (pin "1") (pinfunction "1_1") (pintype "passive"))
    )
    (net (code "34") (name "Net-(D214-A)") (class "Default")
      (node (ref "D214") (pin "1") (pinfunction "A_1") (pintype "passive"))
      (node (ref "S214") (pin "2") (pinfunction "2_2") (pintype "passive"))
    )
    (net (code "35") (name "Net-(D215-A)") (class "Default")
      (node (ref "D215") (pin "1") (pinfunction "A_1") (pintype "passive"))
      (node (ref "S215") (pin "1") (pinfunction "1_1") (pintype "passive"))
    )
    (net (code "36") (name "Net-(D216-A)") (class "Default")
      (node (ref "D216") (pin "1") (pinfunction "A_1") (pintype "passive"))
      (node (ref "S216") (pin "1") (pinfunction "1_1") (pintype "passive"))
    )
    (net (code "37") (name "Net-(D217-A)") (class "Default")
      (node (ref "D217") (pin "1") (pinfunction "A_1") (pintype "passive"))
      (node (ref "S217") (pin "1") (pinfunction "1_1") (pintype "passive"))
    )
    (net (code "38") (name "Net-(D218-A)") (class "Default")
      (node (ref "D218") (pin "1") (pinfunction "A_1") (pintype "passive"))
      (node (ref "S218") (pin "1") (pinfunction "1_1") (pintype "passive"))
    )
    (net (code "39") (name "Net-(D219-A)") (class "Default")
      (node (ref "D219") (pin "1") (pinfunction "A_1") (pintype "passive"))
      (node (ref "S219") (pin "1") (pinfunction "1_1") (pintype "passive"))
    )
    (net (code "40") (name "Net-(D220-A)") (class "Default")
      (node (ref "D220") (pin "1") (pinfunction "A_1") (pintype "passive"))
      (node (ref "S220") (pin "1") (pinfunction "1_1") (pintype "passive"))
    )
    (net (code "41") (name "Net-(D221-A)") (class "Default")
      (node (ref "D221") (pin "1") (pinfunction "A_1") (pintype "passive"))
      (node (ref "S221") (pin "1") (pinfunction "1_1") (pintype "passive"))
    )
    (net (code "42") (name "Net-(D222-A)") (class "Default")
      (node (ref "D222") (pin "1") (pinfunction "A_1") (pintype "passive"))
      (node (ref "S222") (pin "1") (pinfunction "1_1") (pintype "passive"))
    )
    (net (code "43") (name "Net-(D223-A)") (class "Default")
      (node (ref "D223") (pin "1") (pinfunction "A_1") (pintype "passive"))
      (node (ref "S223") (pin "1") (pinfunction "1_1") (pintype "passive"))
    )
    (net (code "44") (name "Net-(D224-A)") (class "Default")
      (node (ref "D224") (pin "1") (pinfunction "A_1") (pintype "passive"))
      (node (ref "S224") (pin "1") (pinfunction "1_1") (pintype "passive"))
    )
    (net (code "45") (name "Net-(D225-A)") (class "Default")
      (node (ref "D225") (pin "1") (pinfunction "A_1") (pintype "passive"))
      (node (ref "S225") (pin "1") (pinfunction "1_1") (pintype "passive"))
    )
    (net (code "46") (name "Net-(D226-A)") (class "Default")
      (node (ref "D226") (pin "1") (pinfunction "A_1") (pintype "passive"))
      (node (ref "S226") (pin "1") (pinfunction "1_1") (pintype "passive"))
    )
    (net (code "47") (name "Net-(D227-A)") (class "Default")
      (node (ref "D227") (pin "1") (pinfunction "A_1") (pintype "passive"))
      (node (ref "S227") (pin "1") (pinfunction "1_1") (pintype "passive"))
    )
    (net (code "48") (name "Net-(D229-A)") (class "Default")
      (node (ref "D229") (pin "1") (pinfunction "A_1") (pintype "passive"))
      (node (ref "S229") (pin "1") (pinfunction "1_1") (pintype "passive"))
      (node (ref "S229_1") (pin "2") (pinfunction "2_2") (pintype "passive"))
    )
    (net (code "49") (name "Net-(D230-A)") (class "Default")
      (node (ref "D230") (pin "1") (pinfunction "A_1") (pintype "passive"))
      (node (ref "S230") (pin "1") (pinfunction "1_1") (pintype "passive"))
    )
    (net (code "50") (name "Net-(D231-A)") (class "Default")
      (node (ref "D231") (pin "1") (pinfunction "A_1") (pintype "passive"))
      (node (ref "S231") (pin "1") (pinfunction "1_1") (pintype "passive"))
    )
    (net (code "51") (name "Net-(D232-A)") (class "Default")
      (node (ref "D232") (pin "1") (pinfunction "A_1") (pintype "passive"))
      (node (ref "S232") (pin "1") (pinfunction "1_1") (pintype "passive"))
    )
    (net (code "52") (name "Net-(D233-A)") (class "Default")
      (node (ref "D233") (pin "1") (pinfunction "A_1") (pintype "passive"))
      (node (ref "S233") (pin "1") (pinfunction "1_1") (pintype "passive"))
    )
    (net (code "53") (name "Net-(D234-A)") (class "Default")
      (node (ref "D234") (pin "1") (pinfunction "A_1") (pintype "passive"))
      (node (ref "S234") (pin "1") (pinfunction "1_1") (pintype "passive"))
    )
    (net (code "54") (name "Net-(D235-A)") (class "Default")
      (node (ref "D235") (pin "1") (pinfunction "A_1") (pintype "passive"))
      (node (ref "S235") (pin "1") (pinfunction "1_1") (pintype "passive"))
    )
    (net (code "55") (name "Net-(D236-A)") (class "Default")
      (node (ref "D236") (pin "1") (pinfunction "A_1") (pintype "passive"))
      (node (ref "S236") (pin "1") (pinfunction "1_1") (pintype "passive"))
    )
    (net (code "56") (name "Net-(D237-A)") (class "Default")
      (node (ref "D237") (pin "1") (pinfunction "A_1") (pintype "passive"))
      (node (ref "S237") (pin "1") (pinfunction "1_1") (pintype "passive"))
    )
    (net (code "57") (name "Net-(D238-A)") (class "Default")
      (node (ref "D238") (pin "1") (pinfunction "A_1") (pintype "passive"))
      (node (ref "S238") (pin "1") (pinfunction "1_1") (pintype "passive"))
    )
    (net (code "58") (name "Net-(D239-A)") (class "Default")
      (node (ref "D239") (pin "1") (pinfunction "A_1") (pintype "passive"))
      (node (ref "S239") (pin "1") (pinfunction "1_1") (pintype "passive"))
    )
    (net (code "59") (name "Net-(D240-A)") (class "Default")
      (node (ref "D240") (pin "1") (pinfunction "A_1") (pintype "passive"))
      (node (ref "S240") (pin "1") (pinfunction "1_1") (pintype "passive"))
    )
    (net (code "60") (name "Net-(D241-A)") (class "Default")
      (node (ref "D241") (pin "1") (pinfunction "A_1") (pintype "passive"))
      (node (ref "S242") (pin "2") (pinfunction "2_2") (pintype "passive"))
    )
    (net (code "61") (name "Net-(D242-A)") (class "Default")
      (node (ref "D242") (pin "1") (pinfunction "A_1") (pintype "passive"))
      (node (ref "S228") (pin "1") (pinfunction "1_1") (pintype "passive"))
    )
    (net (code "62") (name "Net-(D243-A)") (class "Default")
      (node (ref "D243") (pin "1") (pinfunction "A_1") (pintype "passive"))
      (node (ref "S243") (pin "1") (pinfunction "1_1") (pintype "passive"))
    )
    (net (code "63") (name "Net-(D245-A)") (class "Default")
      (node (ref "D245") (pin "1") (pinfunction "A_1") (pintype "passive"))
      (node (ref "S245") (pin "1") (pinfunction "1_1") (pintype "passive"))
    )
    (net (code "64") (name "Net-(D246-A)") (class "Default")
      (node (ref "D246") (pin "1") (pinfunction "A_1") (pintype "passive"))
      (node (ref "S246") (pin "1") (pinfunction "1_1") (pintype "passive"))
    )
    (net (code "65") (name "Net-(D247-A)") (class "Default")
      (node (ref "D247") (pin "1") (pinfunction "A_1") (pintype "passive"))
      (node (ref "S247") (pin "1") (pinfunction "1_1") (pintype "passive"))
    )
    (net (code "66") (name "Net-(D248-A)") (class "Default")
      (node (ref "D248") (pin "1") (pinfunction "A_1") (pintype "passive"))
      (node (ref "S248") (pin "1") (pinfunction "1_1") (pintype "passive"))
    )
    (net (code "67") (name "Net-(D249-A)") (class "Default")
      (node (ref "D249") (pin "1") (pinfunction "A_1") (pintype "passive"))
      (node (ref "S249") (pin "1") (pinfunction "1_1") (pintype "passive"))
    )
    (net (code "68") (name "Net-(D250-A)") (class "Default")
      (node (ref "D250") (pin "1") (pinfunction "A_1") (pintype "passive"))
      (node (ref "S250") (pin "1") (pinfunction "1_1") (pintype "passive"))
    )
    (net (code "69") (name "Net-(D251-A)") (class "Default")
      (node (ref "D251") (pin "1") (pinfunction "A_1") (pintype "passive"))
      (node (ref "S251") (pin "1") (pinfunction "1_1") (pintype "passive"))
    )
    (net (code "70") (name "Net-(D252-A)") (class "Default")
      (node (ref "D252") (pin "1") (pinfunction "A_1") (pintype "passive"))
      (node (ref "S252") (pin "1") (pinfunction "1_1") (pintype "passive"))
    )
    (net (code "71") (name "Net-(D253-A)") (class "Default")
      (node (ref "D253") (pin "1") (pinfunction "A_1") (pintype "passive"))
      (node (ref "S253") (pin "1") (pinfunction "1_1") (pintype "passive"))
    )
    (net (code "72") (name "Net-(D254-A)") (class "Default")
      (node (ref "D254") (pin "1") (pinfunction "A_1") (pintype "passive"))
      (node (ref "S254") (pin "1") (pinfunction "1_1") (pintype "passive"))
    )
    (net (code "73") (name "Net-(D255-A)") (class "Default")
      (node (ref "D255") (pin "1") (pinfunction "A_1") (pintype "passive"))
      (node (ref "S256") (pin "1") (pinfunction "1_1") (pintype "passive"))
    )
    (net (code "74") (name "Net-(D256-A)") (class "Default")
      (node (ref "D256") (pin "1") (pinfunction "A_1") (pintype "passive"))
      (node (ref "S269") (pin "1") (pinfunction "1_1") (pintype "passive"))
    )
    (net (code "75") (name "Net-(D257-A)") (class "Default")
      (node (ref "D257") (pin "1") (pinfunction "A_1") (pintype "passive"))
      (node (ref "S257") (pin "2") (pinfunction "2_2") (pintype "passive"))
    )
    (net (code "76") (name "Net-(D258-A)") (class "Default")
      (node (ref "D258") (pin "1") (pinfunction "A_1") (pintype "passive"))
      (node (ref "S258") (pin "1") (pinfunction "1_1") (pintype "passive"))
    )
    (net (code "77") (name "Net-(D260-A)") (class "Default")
      (node (ref "D260") (pin "1") (pinfunction "A_1") (pintype "passive"))
      (node (ref "S260") (pin "1") (pinfunction "1_1") (pintype "passive"))
    )
    (net (code "78") (name "Net-(D261-A)") (class "Default")
      (node (ref "D261") (pin "1") (pinfunction "A_1") (pintype "passive"))
      (node (ref "S261") (pin "1") (pinfunction "1_1") (pintype "passive"))
    )
    (net (code "79") (name "Net-(D262-A)") (class "Default")
      (node (ref "D262") (pin "1") (pinfunction "A_1") (pintype "passive"))
      (node (ref "S262") (pin "2") (pinfunction "2_2") (pintype "passive"))
    )
    (net (code "80") (name "Net-(D263-A)") (class "Default")
      (node (ref "D263") (pin "1") (pinfunction "A_1") (pintype "passive"))
      (node (ref "S263") (pin "1") (pinfunction "1_1") (pintype "passive"))
    )
    (net (code "81") (name "Net-(D264-A)") (class "Default")
      (node (ref "D264") (pin "1") (pinfunction "A_1") (pintype "passive"))
      (node (ref "S265") (pin "1") (pinfunction "1_1") (pintype "passive"))
    )
    (net (code "82") (name "Net-(D265-A)") (class "Default")
      (node (ref "D265") (pin "1") (pinfunction "A_1") (pintype "passive"))
      (node (ref "S241") (pin "2") (pinfunction "2_2") (pintype "passive"))
    )
    (net (code "83") (name "Net-(D266-A)") (class "Default")
      (node (ref "D266") (pin "1") (pinfunction "A_1") (pintype "passive"))
      (node (ref "S266") (pin "1") (pinfunction "1_1") (pintype "passive"))
    )
    (net (code "84") (name "unconnected-(STAB1-Pad1)") (class "Default")
      (node (ref "STAB1") (pin "1") (pinfunction "1_1") (pintype "passive"))
    )
    (net (code "85") (name "unconnected-(STAB2-Pad1)") (class "Default")
      (node (ref "STAB2") (pin "1") (pinfunction "1_1") (pintype "passive"))
    )
    (net (code "86") (name "unconnected-(STAB3-Pad1)") (class "Default")
      (node (ref "STAB3") (pin "1") (pinfunction "1_1") (pintype "passive"))
    )
    (net (code "87") (name "unconnected-(STAB4-Pad1)") (class "Default")
      (node (ref "STAB4") (pin "1") (pinfunction "1_1") (pintype "passive"))
    )
    (net (code "88") (name "unconnected-(STAB5-Pad1)") (class "Default")
      (node (ref "STAB5") (pin "1") (pinfunction "1_1") (pintype "passive"))
    )
    (net (code "89") (name "unconnected-(STAB6-Pad1)") (class "Default")
      (node (ref "STAB6") (pin "1") (pinfunction "1_1") (pintype "passive"))
    )
    (net (code "90") (name "unconnected-(STAB7-Pad1)") (class "Default")
      (node (ref "STAB7") (pin "1") (pinfunction "1_1") (pintype "passive"))
    )
  )
)
